# USBduino_Max.net
KiCad netlist of a schematic drawn in EAGLE
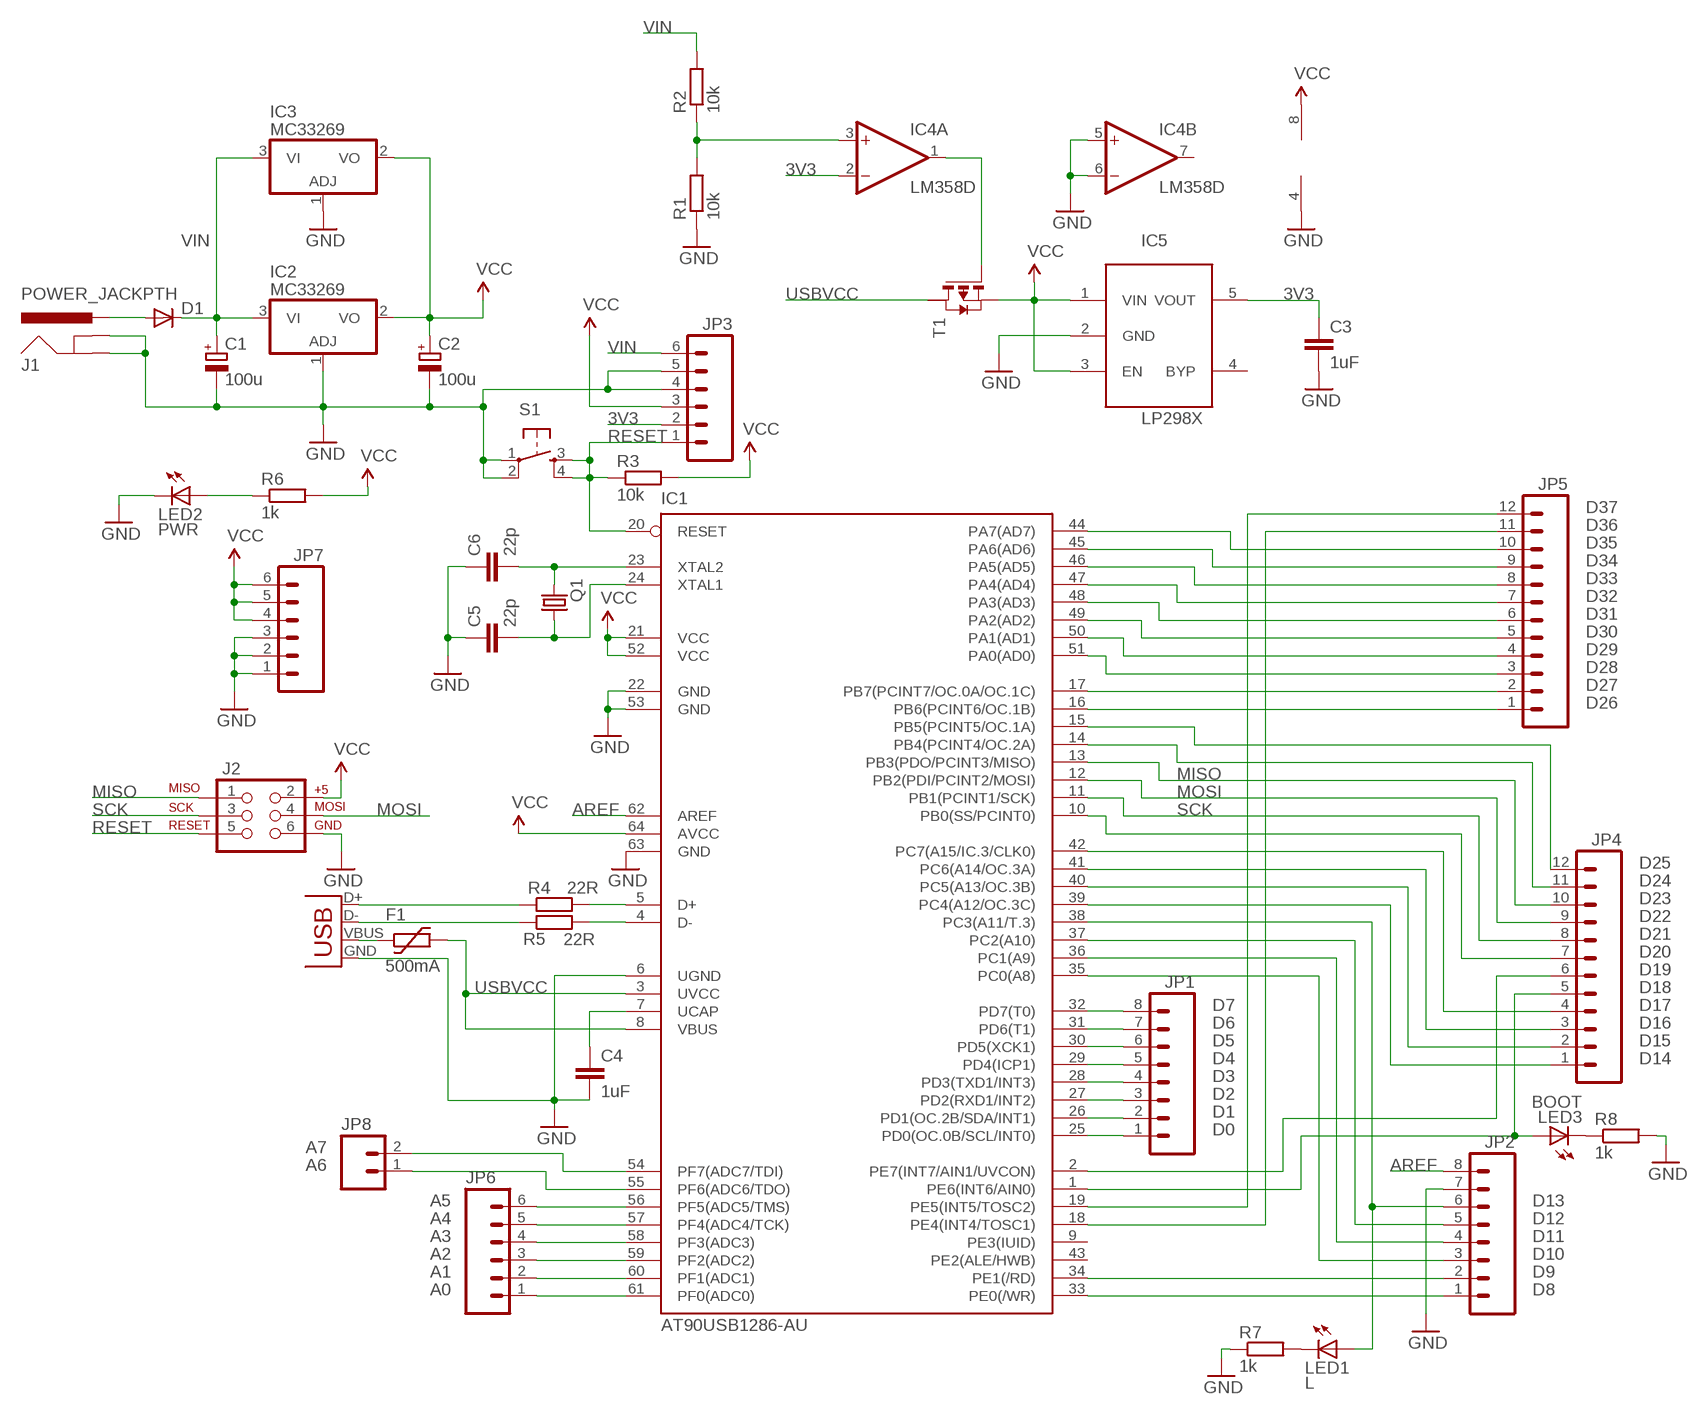
[diagram p0: schematic, sheet 1]

(export (version "E")
  (design (tool "Eeschema 10.0.6"))
  (components
    (comp (ref "C1")
      (value "100u")
      (footprint "eagle-import:PANASONIC_C")
      (libsource (lib "eagle-import") (part "CPOL-EUC"))
    )
    (comp (ref "C2")
      (value "100u")
      (footprint "eagle-import:PANASONIC_C")
      (libsource (lib "eagle-import") (part "CPOL-EUC"))
    )
    (comp (ref "C3")
      (value "1uF")
      (footprint "eagle-import:C0805")
      (libsource (lib "eagle-import") (part "C-EUC0805"))
    )
    (comp (ref "C4")
      (value "1uF")
      (footprint "eagle-import:C0805")
      (libsource (lib "eagle-import") (part "C-EUC0805"))
    )
    (comp (ref "C5")
      (value "22p")
      (footprint "eagle-import:C0805")
      (libsource (lib "eagle-import") (part "C-EUC0805"))
    )
    (comp (ref "C6")
      (value "22p")
      (footprint "eagle-import:C0805")
      (libsource (lib "eagle-import") (part "C-EUC0805"))
    )
    (comp (ref "D1")
      (value "DIODE-SMB")
      (footprint "eagle-import:SMB")
      (libsource (lib "eagle-import") (part "DIODE-SMB"))
    )
    (comp (ref "F1")
      (value "500mA")
      (footprint "eagle-import:1812L")
      (libsource (lib "eagle-import") (part "1812L"))
    )
    (comp (ref "IC1")
      (value "AT90USB1286-AU")
      (footprint "eagle-import:TQFP64")
      (libsource (lib "eagle-import") (part "AT90USB1287-AU"))
    )
    (comp (ref "IC2")
      (value "MC33269")
      (footprint "eagle-import:DPACK")
      (libsource (lib "eagle-import") (part "MC33269?D-5.0"))
    )
    (comp (ref "IC3")
      (value "MC33269")
      (footprint "eagle-import:DPACK")
      (libsource (lib "eagle-import") (part "MC33269?D-5.0"))
    )
    (comp (ref "IC4")
      (value "LM358D")
      (footprint "eagle-import:SO08")
      (libsource (lib "eagle-import") (part "LM358D"))
    )
    (comp (ref "IC5")
      (value "LP2985")
      (footprint "eagle-import:SOT23-5L")
      (libsource (lib "eagle-import") (part "LP298XS"))
    )
    (comp (ref "J1")
      (value "POWER_JACKPTH")
      (footprint "eagle-import:POWER_JACK_PTH")
      (libsource (lib "eagle-import") (part "POWER_JACKPTH"))
    )
    (comp (ref "J2")
      (value "AVR_SPI_PRG_6PTH")
      (footprint "eagle-import:2X3")
      (libsource (lib "eagle-import") (part "AVR_SPI_PRG_6PTH"))
    )
    (comp (ref "JP1")
      (value "M08")
      (footprint "eagle-import:1X08")
      (libsource (lib "eagle-import") (part "M08"))
    )
    (comp (ref "JP2")
      (value "M08")
      (footprint "eagle-import:1X08")
      (libsource (lib "eagle-import") (part "M08"))
    )
    (comp (ref "JP3")
      (value "M06SIP")
      (footprint "eagle-import:1X06")
      (libsource (lib "eagle-import") (part "M06SIP"))
    )
    (comp (ref "JP4")
      (value "M12PTH")
      (footprint "eagle-import:1X12")
      (libsource (lib "eagle-import") (part "M12PTH"))
    )
    (comp (ref "JP5")
      (value "M12PTH")
      (footprint "eagle-import:1X12")
      (libsource (lib "eagle-import") (part "M12PTH"))
    )
    (comp (ref "JP6")
      (value "M06SIP")
      (footprint "eagle-import:1X06")
      (libsource (lib "eagle-import") (part "M06SIP"))
    )
    (comp (ref "JP7")
      (value "M06SIP")
      (footprint "eagle-import:1X06")
      (libsource (lib "eagle-import") (part "M06SIP"))
    )
    (comp (ref "JP8")
      (value "M02PTH")
      (footprint "eagle-import:1X02")
      (libsource (lib "eagle-import") (part "M02PTH"))
    )
    (comp (ref "LED1")
      (value "L")
      (footprint "eagle-import:LED-1206")
      (libsource (lib "eagle-import") (part "LED1206"))
    )
    (comp (ref "LED2")
      (value "PWR")
      (footprint "eagle-import:LED-1206")
      (libsource (lib "eagle-import") (part "LED1206"))
    )
    (comp (ref "LED3")
      (value "BOOT")
      (footprint "eagle-import:LED-1206")
      (libsource (lib "eagle-import") (part "LED1206"))
    )
    (comp (ref "Q1")
      (value "CRYSTALHC49S")
      (footprint "eagle-import:HC49_S")
      (libsource (lib "eagle-import") (part "CRYSTALHC49S"))
    )
    (comp (ref "R1")
      (value "10k")
      (footprint "eagle-import:R0805")
      (libsource (lib "eagle-import") (part "R-EU_R0805"))
    )
    (comp (ref "R2")
      (value "10k")
      (footprint "eagle-import:R0805")
      (libsource (lib "eagle-import") (part "R-EU_R0805"))
    )
    (comp (ref "R3")
      (value "10k")
      (footprint "eagle-import:R0805")
      (libsource (lib "eagle-import") (part "R-EU_R0805"))
    )
    (comp (ref "R4")
      (value "22R")
      (footprint "eagle-import:R0805")
      (libsource (lib "eagle-import") (part "R-EU_R0805"))
    )
    (comp (ref "R5")
      (value "22R")
      (footprint "eagle-import:R0805")
      (libsource (lib "eagle-import") (part "R-EU_R0805"))
    )
    (comp (ref "R6")
      (value "1k")
      (footprint "eagle-import:R0805")
      (libsource (lib "eagle-import") (part "R-EU_R0805"))
    )
    (comp (ref "R7")
      (value "1k")
      (footprint "eagle-import:R0805")
      (libsource (lib "eagle-import") (part "R-EU_R0805"))
    )
    (comp (ref "R8")
      (value "1k")
      (footprint "eagle-import:R0805")
      (libsource (lib "eagle-import") (part "R-EU_R0805"))
    )
    (comp (ref "S1")
      (value "TAC_SWITCHPTH")
      (footprint "eagle-import:TACTILE-PTH")
      (libsource (lib "eagle-import") (part "TAC_SWITCHPTH"))
    )
    (comp (ref "T1")
      (value "PMOSSOT223")
      (footprint "eagle-import:SOT223")
      (libsource (lib "eagle-import") (part "PMOSSOT223"))
    )
    (comp (ref "X1")
      (value "USBPTH")
      (footprint "eagle-import:USB-B-PTH")
      (libsource (lib "eagle-import") (part "USBPTH"))
    )
  )
  (nets
    (net (code "1") (name "/3V3") (class "Default")
      (node (ref "C3") (pin "1") (pinfunction "1_1") (pintype "passive"))
      (node (ref "IC4") (pin "2") (pinfunction "-IN_2") (pintype "input"))
      (node (ref "IC5") (pin "5") (pinfunction "VOUT_5") (pintype "bidirectional"))
      (node (ref "JP3") (pin "2") (pinfunction "2_2") (pintype "passive"))
    )
    (net (code "2") (name "/AREF") (class "Default")
      (node (ref "IC1") (pin "62") (pinfunction "AREF_62") (pintype "bidirectional"))
      (node (ref "JP2") (pin "8") (pinfunction "8_8") (pintype "passive"))
    )
    (net (code "3") (name "/MISO") (class "Default")
      (node (ref "IC1") (pin "13") (pinfunction "PB3(PDO/PCINT3/MISO)_13") (pintype "bidirectional"))
      (node (ref "J2") (pin "1") (pinfunction "1_1") (pintype "passive"))
      (node (ref "JP4") (pin "10") (pinfunction "10_10") (pintype "passive"))
    )
    (net (code "4") (name "/MOSI") (class "Default")
      (node (ref "IC1") (pin "12") (pinfunction "PB2(PDI/PCINT2/MOSI)_12") (pintype "bidirectional"))
      (node (ref "J2") (pin "4") (pinfunction "4_4") (pintype "passive"))
      (node (ref "JP4") (pin "9") (pinfunction "9_9") (pintype "passive"))
    )
    (net (code "5") (name "/RESET") (class "Default")
      (node (ref "IC1") (pin "20") (pinfunction "RESET_20") (pintype "input"))
      (node (ref "J2") (pin "5") (pinfunction "5_5") (pintype "passive"))
      (node (ref "JP3") (pin "1") (pinfunction "1_1") (pintype "passive"))
      (node (ref "R3") (pin "1") (pinfunction "1_1") (pintype "passive"))
      (node (ref "S1") (pin "3") (pinfunction "3_3") (pintype "passive"))
      (node (ref "S1") (pin "4") (pinfunction "4_4") (pintype "passive"))
    )
    (net (code "6") (name "/SCK") (class "Default")
      (node (ref "IC1") (pin "11") (pinfunction "PB1(PCINT1/SCK)_11") (pintype "bidirectional"))
      (node (ref "J2") (pin "3") (pinfunction "3_3") (pintype "passive"))
      (node (ref "JP4") (pin "8") (pinfunction "8_8") (pintype "passive"))
    )
    (net (code "7") (name "/USBVCC") (class "Default")
      (node (ref "F1") (pin "P$2") (pinfunction "2_P$2") (pintype "passive"))
      (node (ref "IC1") (pin "3") (pinfunction "UVCC_3") (pintype "power_in"))
      (node (ref "IC1") (pin "8") (pinfunction "VBUS_8") (pintype "power_in"))
      (node (ref "T1") (pin "2") (pinfunction "D_2") (pintype "passive"))
    )
    (net (code "8") (name "/VIN") (class "Default")
      (node (ref "C1") (pin "+") (pinfunction "+_+") (pintype "passive"))
      (node (ref "D1") (pin "C") (pinfunction "C_C") (pintype "passive"))
      (node (ref "IC2") (pin "3") (pinfunction "VI_3") (pintype "input"))
      (node (ref "IC3") (pin "3") (pinfunction "VI_3") (pintype "input"))
      (node (ref "JP3") (pin "6") (pinfunction "6_6") (pintype "passive"))
      (node (ref "R2") (pin "2") (pinfunction "2_2") (pintype "passive"))
    )
    (net (code "9") (name "GND") (class "Default")
      (node (ref "C1") (pin "-") (pinfunction "-_-") (pintype "passive"))
      (node (ref "C2") (pin "-") (pinfunction "-_-") (pintype "passive"))
      (node (ref "C3") (pin "2") (pinfunction "2_2") (pintype "passive"))
      (node (ref "C4") (pin "2") (pinfunction "2_2") (pintype "passive"))
      (node (ref "C5") (pin "1") (pinfunction "1_1") (pintype "passive"))
      (node (ref "C6") (pin "1") (pinfunction "1_1") (pintype "passive"))
      (node (ref "IC1") (pin "22") (pinfunction "GND_22") (pintype "power_in"))
      (node (ref "IC1") (pin "53") (pinfunction "GND_53") (pintype "power_in"))
      (node (ref "IC1") (pin "6") (pinfunction "UGND_6") (pintype "power_in"))
      (node (ref "IC1") (pin "63") (pinfunction "GND_63") (pintype "power_in"))
      (node (ref "IC2") (pin "1") (pinfunction "ADJ_1") (pintype "input"))
      (node (ref "IC3") (pin "1") (pinfunction "ADJ_1") (pintype "input"))
      (node (ref "IC4") (pin "4") (pinfunction "V-_4") (pintype "power_in"))
      (node (ref "IC4") (pin "5") (pinfunction "+IN_5") (pintype "input"))
      (node (ref "IC4") (pin "6") (pinfunction "-IN_6") (pintype "input"))
      (node (ref "IC5") (pin "2") (pinfunction "GND_2") (pintype "bidirectional"))
      (node (ref "J1") (pin "GND") (pinfunction "GND_GND") (pintype "bidirectional"))
      (node (ref "J1") (pin "GNDBREAK") (pinfunction "GNDBREAK_GNDBREAK") (pintype "bidirectional"))
      (node (ref "J2") (pin "6") (pinfunction "6_6") (pintype "passive"))
      (node (ref "JP2") (pin "7") (pinfunction "7_7") (pintype "passive"))
      (node (ref "JP3") (pin "4") (pinfunction "4_4") (pintype "passive"))
      (node (ref "JP3") (pin "5") (pinfunction "5_5") (pintype "passive"))
      (node (ref "JP7") (pin "1") (pinfunction "1_1") (pintype "passive"))
      (node (ref "JP7") (pin "2") (pinfunction "2_2") (pintype "passive"))
      (node (ref "JP7") (pin "3") (pinfunction "3_3") (pintype "passive"))
      (node (ref "LED2") (pin "C") (pinfunction "C_C") (pintype "passive"))
      (node (ref "R1") (pin "1") (pinfunction "1_1") (pintype "passive"))
      (node (ref "R7") (pin "1") (pinfunction "1_1") (pintype "passive"))
      (node (ref "R8") (pin "2") (pinfunction "2_2") (pintype "passive"))
      (node (ref "S1") (pin "1") (pinfunction "1_1") (pintype "passive"))
      (node (ref "S1") (pin "2") (pinfunction "2_2") (pintype "passive"))
      (node (ref "X1") (pin "GND") (pinfunction "GND_GND") (pintype "bidirectional"))
    )
    (net (code "10") (name "Net-(D1-PadA)") (class "Default")
      (node (ref "D1") (pin "A") (pinfunction "A_A") (pintype "passive"))
      (node (ref "J1") (pin "PWR") (pinfunction "PWR_PWR") (pintype "bidirectional"))
    )
    (net (code "11") (name "Net-(F1-1)") (class "Default")
      (node (ref "F1") (pin "P$1") (pinfunction "1_P$1") (pintype "passive"))
      (node (ref "X1") (pin "VBUS") (pinfunction "VBUS_VBUS") (pintype "bidirectional"))
    )
    (net (code "12") (name "Net-(IC1-D+)") (class "Default")
      (node (ref "IC1") (pin "5") (pinfunction "D+_5") (pintype "bidirectional"))
      (node (ref "R4") (pin "2") (pinfunction "2_2") (pintype "passive"))
    )
    (net (code "13") (name "Net-(IC1-D-)") (class "Default")
      (node (ref "IC1") (pin "4") (pinfunction "D-_4") (pintype "bidirectional"))
      (node (ref "R5") (pin "2") (pinfunction "2_2") (pintype "passive"))
    )
    (net (code "14") (name "Net-(IC1-PA0(AD0))") (class "Default")
      (node (ref "IC1") (pin "51") (pinfunction "PA0(AD0)_51") (pintype "bidirectional"))
      (node (ref "JP5") (pin "3") (pinfunction "3_3") (pintype "passive"))
    )
    (net (code "15") (name "Net-(IC1-PA1(AD1))") (class "Default")
      (node (ref "IC1") (pin "50") (pinfunction "PA1(AD1)_50") (pintype "bidirectional"))
      (node (ref "JP5") (pin "4") (pinfunction "4_4") (pintype "passive"))
    )
    (net (code "16") (name "Net-(IC1-PA2(AD2))") (class "Default")
      (node (ref "IC1") (pin "49") (pinfunction "PA2(AD2)_49") (pintype "bidirectional"))
      (node (ref "JP5") (pin "5") (pinfunction "5_5") (pintype "passive"))
    )
    (net (code "17") (name "Net-(IC1-PA3(AD3))") (class "Default")
      (node (ref "IC1") (pin "48") (pinfunction "PA3(AD3)_48") (pintype "bidirectional"))
      (node (ref "JP5") (pin "6") (pinfunction "6_6") (pintype "passive"))
    )
    (net (code "18") (name "Net-(IC1-PA4(AD4))") (class "Default")
      (node (ref "IC1") (pin "47") (pinfunction "PA4(AD4)_47") (pintype "bidirectional"))
      (node (ref "JP5") (pin "7") (pinfunction "7_7") (pintype "passive"))
    )
    (net (code "19") (name "Net-(IC1-PA5(AD5))") (class "Default")
      (node (ref "IC1") (pin "46") (pinfunction "PA5(AD5)_46") (pintype "bidirectional"))
      (node (ref "JP5") (pin "8") (pinfunction "8_8") (pintype "passive"))
    )
    (net (code "20") (name "Net-(IC1-PA6(AD6))") (class "Default")
      (node (ref "IC1") (pin "45") (pinfunction "PA6(AD6)_45") (pintype "bidirectional"))
      (node (ref "JP5") (pin "9") (pinfunction "9_9") (pintype "passive"))
    )
    (net (code "21") (name "Net-(IC1-PA7(AD7))") (class "Default")
      (node (ref "IC1") (pin "44") (pinfunction "PA7(AD7)_44") (pintype "bidirectional"))
      (node (ref "JP5") (pin "10") (pinfunction "10_10") (pintype "passive"))
    )
    (net (code "22") (name "Net-(IC1-PB0(SS{slash}PCINT0))") (class "Default")
      (node (ref "IC1") (pin "10") (pinfunction "PB0(SS/PCINT0)_10") (pintype "bidirectional"))
      (node (ref "JP4") (pin "7") (pinfunction "7_7") (pintype "passive"))
    )
    (net (code "23") (name "Net-(IC1-PB4(PCINT4{slash}OC.2A))") (class "Default")
      (node (ref "IC1") (pin "14") (pinfunction "PB4(PCINT4/OC.2A)_14") (pintype "bidirectional"))
      (node (ref "JP4") (pin "11") (pinfunction "11_11") (pintype "passive"))
    )
    (net (code "24") (name "Net-(IC1-PB5(PCINT5{slash}OC.1A))") (class "Default")
      (node (ref "IC1") (pin "15") (pinfunction "PB5(PCINT5/OC.1A)_15") (pintype "bidirectional"))
      (node (ref "JP4") (pin "12") (pinfunction "12_12") (pintype "passive"))
    )
    (net (code "25") (name "Net-(IC1-PB6(PCINT6{slash}OC.1B))") (class "Default")
      (node (ref "IC1") (pin "16") (pinfunction "PB6(PCINT6/OC.1B)_16") (pintype "bidirectional"))
      (node (ref "JP5") (pin "1") (pinfunction "1_1") (pintype "passive"))
    )
    (net (code "26") (name "Net-(IC1-PB7(PCINT7{slash}OC.0A{slash}OC.1C))") (class "Default")
      (node (ref "IC1") (pin "17") (pinfunction "PB7(PCINT7/OC.0A/OC.1C)_17") (pintype "bidirectional"))
      (node (ref "JP5") (pin "2") (pinfunction "2_2") (pintype "passive"))
    )
    (net (code "27") (name "Net-(IC1-PC0(A8))") (class "Default")
      (node (ref "IC1") (pin "35") (pinfunction "PC0(A8)_35") (pintype "bidirectional"))
      (node (ref "JP2") (pin "3") (pinfunction "3_3") (pintype "passive"))
    )
    (net (code "28") (name "Net-(IC1-PC1(A9))") (class "Default")
      (node (ref "IC1") (pin "36") (pinfunction "PC1(A9)_36") (pintype "bidirectional"))
      (node (ref "JP2") (pin "4") (pinfunction "4_4") (pintype "passive"))
    )
    (net (code "29") (name "Net-(IC1-PC2(A10))") (class "Default")
      (node (ref "IC1") (pin "37") (pinfunction "PC2(A10)_37") (pintype "bidirectional"))
      (node (ref "JP2") (pin "5") (pinfunction "5_5") (pintype "passive"))
    )
    (net (code "30") (name "Net-(IC1-PC3(A11{slash}T.3))") (class "Default")
      (node (ref "IC1") (pin "38") (pinfunction "PC3(A11/T.3)_38") (pintype "bidirectional"))
      (node (ref "JP2") (pin "6") (pinfunction "6_6") (pintype "passive"))
      (node (ref "LED1") (pin "A") (pinfunction "A_A") (pintype "passive"))
    )
    (net (code "31") (name "Net-(IC1-PC4(A12{slash}OC.3C))") (class "Default")
      (node (ref "IC1") (pin "39") (pinfunction "PC4(A12/OC.3C)_39") (pintype "bidirectional"))
      (node (ref "JP4") (pin "1") (pinfunction "1_1") (pintype "passive"))
    )
    (net (code "32") (name "Net-(IC1-PC5(A13{slash}OC.3B))") (class "Default")
      (node (ref "IC1") (pin "40") (pinfunction "PC5(A13/OC.3B)_40") (pintype "bidirectional"))
      (node (ref "JP4") (pin "2") (pinfunction "2_2") (pintype "passive"))
    )
    (net (code "33") (name "Net-(IC1-PC6(A14{slash}OC.3A))") (class "Default")
      (node (ref "IC1") (pin "41") (pinfunction "PC6(A14/OC.3A)_41") (pintype "bidirectional"))
      (node (ref "JP4") (pin "3") (pinfunction "3_3") (pintype "passive"))
    )
    (net (code "34") (name "Net-(IC1-PC7(A15{slash}IC.3{slash}CLK0))") (class "Default")
      (node (ref "IC1") (pin "42") (pinfunction "PC7(A15/IC.3/CLK0)_42") (pintype "bidirectional"))
      (node (ref "JP4") (pin "4") (pinfunction "4_4") (pintype "passive"))
    )
    (net (code "35") (name "Net-(IC1-PD0(OC.0B{slash}SCL{slash}INT0))") (class "Default")
      (node (ref "IC1") (pin "25") (pinfunction "PD0(OC.0B/SCL/INT0)_25") (pintype "bidirectional"))
      (node (ref "JP1") (pin "1") (pinfunction "1_1") (pintype "passive"))
    )
    (net (code "36") (name "Net-(IC1-PD1(OC.2B{slash}SDA{slash}INT1))") (class "Default")
      (node (ref "IC1") (pin "26") (pinfunction "PD1(OC.2B/SDA/INT1)_26") (pintype "bidirectional"))
      (node (ref "JP1") (pin "2") (pinfunction "2_2") (pintype "passive"))
    )
    (net (code "37") (name "Net-(IC1-PD2(RXD1{slash}INT2))") (class "Default")
      (node (ref "IC1") (pin "27") (pinfunction "PD2(RXD1/INT2)_27") (pintype "bidirectional"))
      (node (ref "JP1") (pin "3") (pinfunction "3_3") (pintype "passive"))
    )
    (net (code "38") (name "Net-(IC1-PD3(TXD1{slash}INT3))") (class "Default")
      (node (ref "IC1") (pin "28") (pinfunction "PD3(TXD1/INT3)_28") (pintype "bidirectional"))
      (node (ref "JP1") (pin "4") (pinfunction "4_4") (pintype "passive"))
    )
    (net (code "39") (name "Net-(IC1-PD4(ICP1))") (class "Default")
      (node (ref "IC1") (pin "29") (pinfunction "PD4(ICP1)_29") (pintype "bidirectional"))
      (node (ref "JP1") (pin "5") (pinfunction "5_5") (pintype "passive"))
    )
    (net (code "40") (name "Net-(IC1-PD5(XCK1))") (class "Default")
      (node (ref "IC1") (pin "30") (pinfunction "PD5(XCK1)_30") (pintype "bidirectional"))
      (node (ref "JP1") (pin "6") (pinfunction "6_6") (pintype "passive"))
    )
    (net (code "41") (name "Net-(IC1-PD6(T1))") (class "Default")
      (node (ref "IC1") (pin "31") (pinfunction "PD6(T1)_31") (pintype "bidirectional"))
      (node (ref "JP1") (pin "7") (pinfunction "7_7") (pintype "passive"))
    )
    (net (code "42") (name "Net-(IC1-PD7(T0))") (class "Default")
      (node (ref "IC1") (pin "32") (pinfunction "PD7(T0)_32") (pintype "bidirectional"))
      (node (ref "JP1") (pin "8") (pinfunction "8_8") (pintype "passive"))
    )
    (net (code "43") (name "Net-(IC1-PE0({slash}WR))") (class "Default")
      (node (ref "IC1") (pin "33") (pinfunction "PE0(/WR)_33") (pintype "bidirectional"))
      (node (ref "JP2") (pin "1") (pinfunction "1_1") (pintype "passive"))
    )
    (net (code "44") (name "Net-(IC1-PE1({slash}RD))") (class "Default")
      (node (ref "IC1") (pin "34") (pinfunction "PE1(/RD)_34") (pintype "bidirectional"))
      (node (ref "JP2") (pin "2") (pinfunction "2_2") (pintype "passive"))
    )
    (net (code "45") (name "Net-(IC1-PE4(INT4{slash}TOSC1))") (class "Default")
      (node (ref "IC1") (pin "18") (pinfunction "PE4(INT4/TOSC1)_18") (pintype "bidirectional"))
      (node (ref "JP5") (pin "11") (pinfunction "11_11") (pintype "passive"))
    )
    (net (code "46") (name "Net-(IC1-PE5(INT5{slash}TOSC2))") (class "Default")
      (node (ref "IC1") (pin "19") (pinfunction "PE5(INT5/TOSC2)_19") (pintype "bidirectional"))
      (node (ref "JP5") (pin "12") (pinfunction "12_12") (pintype "passive"))
    )
    (net (code "47") (name "Net-(IC1-PE6(INT6{slash}AIN0))") (class "Default")
      (node (ref "IC1") (pin "1") (pinfunction "PE6(INT6/AIN0)_1") (pintype "bidirectional"))
      (node (ref "JP4") (pin "5") (pinfunction "5_5") (pintype "passive"))
      (node (ref "LED3") (pin "A") (pinfunction "A_A") (pintype "passive"))
    )
    (net (code "48") (name "Net-(IC1-PE7(INT7{slash}AIN1{slash}UVCON))") (class "Default")
      (node (ref "IC1") (pin "2") (pinfunction "PE7(INT7/AIN1/UVCON)_2") (pintype "bidirectional"))
      (node (ref "JP4") (pin "6") (pinfunction "6_6") (pintype "passive"))
    )
    (net (code "49") (name "Net-(IC1-PF0(ADC0))") (class "Default")
      (node (ref "IC1") (pin "61") (pinfunction "PF0(ADC0)_61") (pintype "bidirectional"))
      (node (ref "JP6") (pin "1") (pinfunction "1_1") (pintype "passive"))
    )
    (net (code "50") (name "Net-(IC1-PF1(ADC1))") (class "Default")
      (node (ref "IC1") (pin "60") (pinfunction "PF1(ADC1)_60") (pintype "bidirectional"))
      (node (ref "JP6") (pin "2") (pinfunction "2_2") (pintype "passive"))
    )
    (net (code "51") (name "Net-(IC1-PF2(ADC2))") (class "Default")
      (node (ref "IC1") (pin "59") (pinfunction "PF2(ADC2)_59") (pintype "bidirectional"))
      (node (ref "JP6") (pin "3") (pinfunction "3_3") (pintype "passive"))
    )
    (net (code "52") (name "Net-(IC1-PF3(ADC3))") (class "Default")
      (node (ref "IC1") (pin "58") (pinfunction "PF3(ADC3)_58") (pintype "bidirectional"))
      (node (ref "JP6") (pin "4") (pinfunction "4_4") (pintype "passive"))
    )
    (net (code "53") (name "Net-(IC1-PF4(ADC4{slash}TCK))") (class "Default")
      (node (ref "IC1") (pin "57") (pinfunction "PF4(ADC4/TCK)_57") (pintype "bidirectional"))
      (node (ref "JP6") (pin "5") (pinfunction "5_5") (pintype "passive"))
    )
    (net (code "54") (name "Net-(IC1-PF5(ADC5{slash}TMS))") (class "Default")
      (node (ref "IC1") (pin "56") (pinfunction "PF5(ADC5/TMS)_56") (pintype "bidirectional"))
      (node (ref "JP6") (pin "6") (pinfunction "6_6") (pintype "passive"))
    )
    (net (code "55") (name "Net-(IC1-PF6(ADC6{slash}TDO))") (class "Default")
      (node (ref "IC1") (pin "55") (pinfunction "PF6(ADC6/TDO)_55") (pintype "bidirectional"))
      (node (ref "JP8") (pin "1") (pinfunction "1_1") (pintype "passive"))
    )
    (net (code "56") (name "Net-(IC1-PF7(ADC7{slash}TDI))") (class "Default")
      (node (ref "IC1") (pin "54") (pinfunction "PF7(ADC7/TDI)_54") (pintype "bidirectional"))
      (node (ref "JP8") (pin "2") (pinfunction "2_2") (pintype "passive"))
    )
    (net (code "57") (name "Net-(IC1-UCAP)") (class "Default")
      (node (ref "C4") (pin "1") (pinfunction "1_1") (pintype "passive"))
      (node (ref "IC1") (pin "7") (pinfunction "UCAP_7") (pintype "power_in"))
    )
    (net (code "58") (name "Net-(IC1-XTAL1)") (class "Default")
      (node (ref "C5") (pin "2") (pinfunction "2_2") (pintype "passive"))
      (node (ref "IC1") (pin "24") (pinfunction "XTAL1_24") (pintype "bidirectional"))
      (node (ref "Q1") (pin "1") (pinfunction "1_1") (pintype "passive"))
    )
    (net (code "59") (name "Net-(IC1-XTAL2)") (class "Default")
      (node (ref "C6") (pin "2") (pinfunction "2_2") (pintype "passive"))
      (node (ref "IC1") (pin "23") (pinfunction "XTAL2_23") (pintype "bidirectional"))
      (node (ref "Q1") (pin "2") (pinfunction "2_2") (pintype "passive"))
    )
    (net (code "60") (name "Net-(IC4A-+IN)") (class "Default")
      (node (ref "IC4") (pin "3") (pinfunction "+IN_3") (pintype "input"))
      (node (ref "R1") (pin "2") (pinfunction "2_2") (pintype "passive"))
      (node (ref "R2") (pin "1") (pinfunction "1_1") (pintype "passive"))
    )
    (net (code "61") (name "Net-(IC4A-OUT)") (class "Default")
      (node (ref "IC4") (pin "1") (pinfunction "OUT_1") (pintype "output"))
      (node (ref "T1") (pin "1") (pinfunction "G_1") (pintype "passive"))
    )
    (net (code "62") (name "Net-(LED1-PadC)") (class "Default")
      (node (ref "LED1") (pin "C") (pinfunction "C_C") (pintype "passive"))
      (node (ref "R7") (pin "2") (pinfunction "2_2") (pintype "passive"))
    )
    (net (code "63") (name "Net-(LED2-PadA)") (class "Default")
      (node (ref "LED2") (pin "A") (pinfunction "A_A") (pintype "passive"))
      (node (ref "R6") (pin "1") (pinfunction "1_1") (pintype "passive"))
    )
    (net (code "64") (name "Net-(LED3-PadC)") (class "Default")
      (node (ref "LED3") (pin "C") (pinfunction "C_C") (pintype "passive"))
      (node (ref "R8") (pin "1") (pinfunction "1_1") (pintype "passive"))
    )
    (net (code "65") (name "Net-(R4-Pad1)") (class "Default")
      (node (ref "R4") (pin "1") (pinfunction "1_1") (pintype "passive"))
      (node (ref "X1") (pin "D+") (pinfunction "D+_D+") (pintype "bidirectional"))
    )
    (net (code "66") (name "Net-(R5-Pad1)") (class "Default")
      (node (ref "R5") (pin "1") (pinfunction "1_1") (pintype "passive"))
      (node (ref "X1") (pin "D-") (pinfunction "D-_D-") (pintype "bidirectional"))
    )
    (net (code "67") (name "VCC") (class "Default")
      (node (ref "C2") (pin "+") (pinfunction "+_+") (pintype "passive"))
      (node (ref "IC1") (pin "21") (pinfunction "VCC_21") (pintype "power_in"))
      (node (ref "IC1") (pin "52") (pinfunction "VCC_52") (pintype "power_in"))
      (node (ref "IC1") (pin "64") (pinfunction "AVCC_64") (pintype "bidirectional"))
      (node (ref "IC2") (pin "2") (pinfunction "VO_2") (pintype "passive"))
      (node (ref "IC3") (pin "2") (pinfunction "VO_2") (pintype "passive"))
      (node (ref "IC4") (pin "8") (pinfunction "V+_8") (pintype "power_in"))
      (node (ref "IC5") (pin "1") (pinfunction "VIN_1") (pintype "bidirectional"))
      (node (ref "IC5") (pin "3") (pinfunction "EN_3") (pintype "bidirectional"))
      (node (ref "J2") (pin "2") (pinfunction "2_2") (pintype "passive"))
      (node (ref "JP3") (pin "3") (pinfunction "3_3") (pintype "passive"))
      (node (ref "JP7") (pin "4") (pinfunction "4_4") (pintype "passive"))
      (node (ref "JP7") (pin "5") (pinfunction "5_5") (pintype "passive"))
      (node (ref "JP7") (pin "6") (pinfunction "6_6") (pintype "passive"))
      (node (ref "R3") (pin "2") (pinfunction "2_2") (pintype "passive"))
      (node (ref "R6") (pin "2") (pinfunction "2_2") (pintype "passive"))
      (node (ref "T1") (pin "3") (pinfunction "S_3") (pintype "passive"))
    )
    (net (code "68") (name "unconnected-(IC1-PE2(ALE{slash}HWB)-Pad43)") (class "Default")
      (node (ref "IC1") (pin "43") (pinfunction "PE2(ALE/HWB)_43") (pintype "bidirectional"))
    )
    (net (code "69") (name "unconnected-(IC1-PE3(IUID)-Pad9)") (class "Default")
      (node (ref "IC1") (pin "9") (pinfunction "PE3(IUID)_9") (pintype "bidirectional"))
    )
    (net (code "70") (name "unconnected-(IC4B-OUT-Pad7)") (class "Default")
      (node (ref "IC4") (pin "7") (pinfunction "OUT_7") (pintype "output"))
    )
    (net (code "71") (name "unconnected-(IC5-BYP-Pad4)") (class "Default")
      (node (ref "IC5") (pin "4") (pinfunction "BYP_4") (pintype "bidirectional"))
    )
    (net (code "72") (name "unconnected-(T1-D2-Pad4)") (class "Default")
      (node (ref "T1") (pin "4") (pinfunction "D2_4") (pintype "passive"))
    )
  )
)
